# projet_pcb_bluepill_f103.net
KiCad netlist of a schematic drawn in Altium Designer
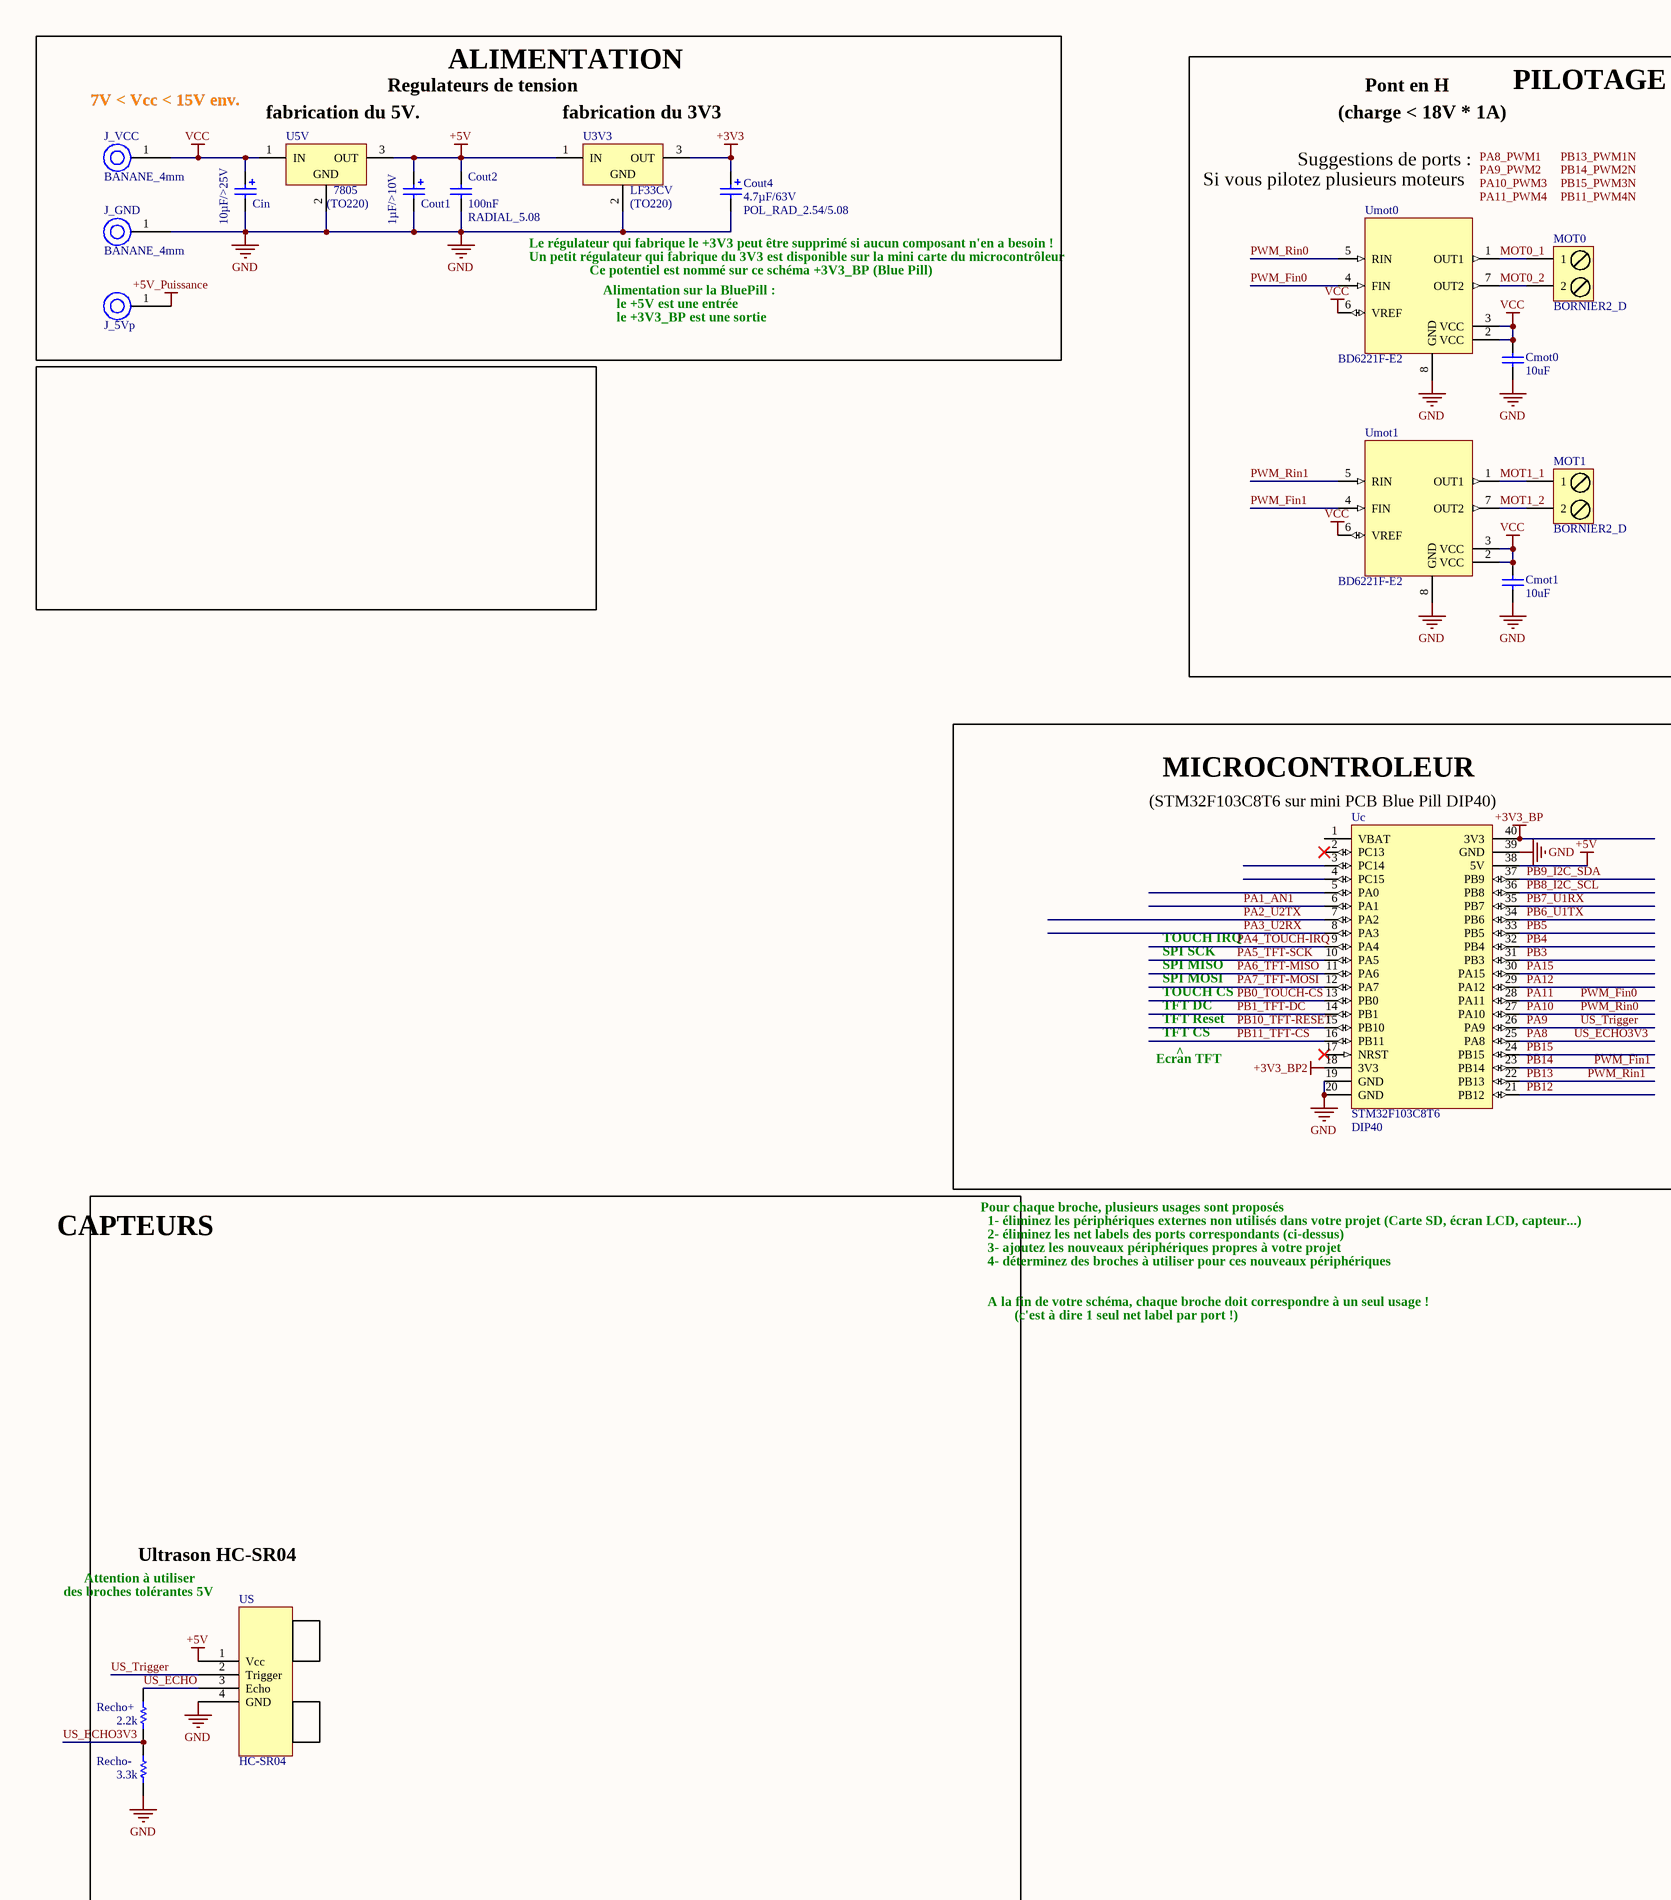
[diagram p0: projet_pcb_bluepill_f103.SchDoc, left]
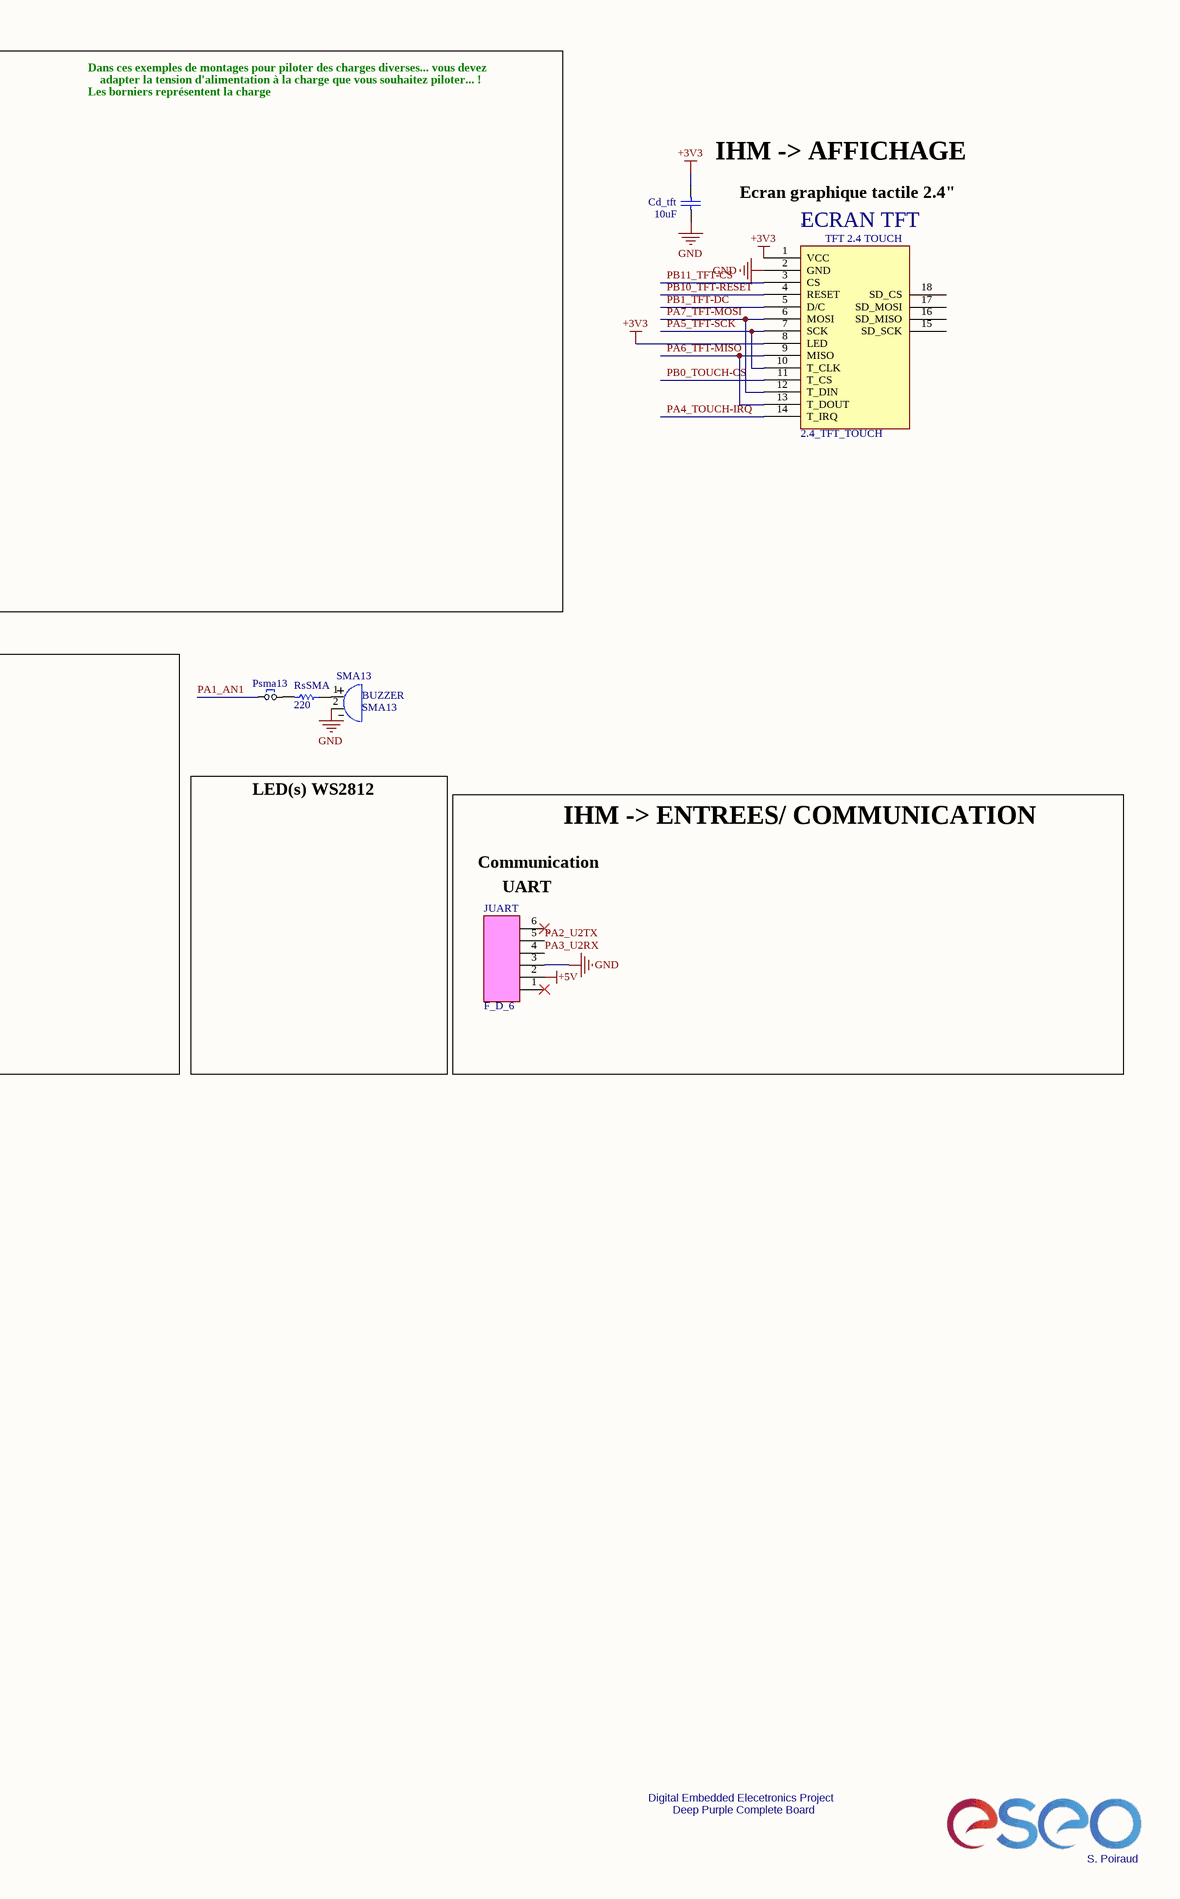
[diagram p1: projet_pcb_bluepill_f103.SchDoc, right]

(export (version "E")
  (design (tool "Eeschema 10.0.6"))
  (components
    (comp (ref "*")
      (value "2.4_TFT_TOUCH")
      (footprint "2.4_TFT_TOUCH")
      (libsource (lib "_ROBOT") (part "2.4_TFT_TOUCH"))
    )
    (comp (ref "Cd_tft")
      (value "10uF")
      (footprint "CONDENSATEUR_POLARISE_ELECTROLYTIQUE_RADIAL_2.54/5.08")
      (description "Capacitor")
      (fields (field (name "PUBLISHER") "Altium Limited"))
      (libsource (lib "_ROBOT") (part "Condensateur"))
    )
    (comp (ref "Cin")
      (value "10µF/>25V")
      (footprint "CONDENSATEUR_POLARISE_ELECTROLYTIQUE_RADIAL_2.0/5.08")
      (description "CONDENSATEUR POLARISE ELECTROLYTIQUE RADIAL 2.0/5.08")
      (fields (field (name "Comment") "CONDENSATEUR_POL_ELECTROLY_RAD_2.0/5.08"))
      (libsource (lib "composants passifs") (part "CONDENSATEUR_POL_ELECTROLY_RAD_2.0/5.08"))
    )
    (comp (ref "Cmot0")
      (value "10uF")
      (footprint "CONDENSATEUR_POLARISE_ELECTROLYTIQUE_RADIAL_2.0/5.08")
      (description "Capacitor")
      (fields (field (name "PUBLISHER") "Altium Limited"))
      (libsource (lib "_ROBOT") (part "Condensateur"))
    )
    (comp (ref "Cmot1")
      (value "10uF")
      (footprint "CONDENSATEUR_POLARISE_ELECTROLYTIQUE_RADIAL_2.0/5.08")
      (description "Capacitor")
      (fields (field (name "PUBLISHER") "Altium Limited"))
      (libsource (lib "_ROBOT") (part "Condensateur"))
    )
    (comp (ref "Cout1")
      (value "1µF/>10V")
      (footprint "CONDENSATEUR_POLARISE_ELECTROLYTIQUE_RADIAL_2.0/5.08")
      (description "CONDENSATEUR POLARISE ELECTROLYTIQUE RADIAL 2.0/5.08")
      (fields (field (name "Comment") "CONDENSATEUR_POL_ELECTROLY_RAD_2.0/5.08"))
      (libsource (lib "composants passifs") (part "CONDENSATEUR_POL_ELECTROLY_RAD_2.0/5.08"))
    )
    (comp (ref "Cout2")
      (value "100nF")
      (footprint "CONDENSATEUR_CERAMIQUE_RADIAL_5.08")
      (description "CONDENSATEUR TRAVERSANT CERAMIQUE RADIAL 5.08mm")
      (fields (field (name "TYPE") "RADIAL_5.08") (field (name "Comment") "CONDENSATEUR_CER_RAD_5.08"))
      (libsource (lib "composants passifs") (part "CONDENSATEUR_CER_RAD_5.08"))
    )
    (comp (ref "Cout4")
      (value "4.7µF/63V")
      (footprint "CONDENSATEUR_POLARISE_ELECTROLYTIQUE_RADIAL_2.54/5.08")
      (description "CONDENSATEUR POLARISE ELECTROLYTIQUE RADIAL 2.54/5.08")
      (fields
        (field (name "TYPE") "POL_RAD_2.54/5.08")
        (field (name "Comment") "CONDENSATEUR_POL_ELECTROLY_RAD_2.54/5.08")
      )
      (libsource (lib "composants passifs") (part "CONDENSATEUR_POL_ELECTROLY_RAD_2.54/5.08"))
    )
    (comp (ref "JUART")
      (value "BARRETTE_6 CONTACTS_1 RANGEE_FEMELLE_DROITE")
      (footprint "BARRETTE_6_F_D")
      (description "BARRETTE 6 CONTACTS 1 RANGEE FEMELLE DROITE")
      (fields (field (name "TYPE") "F_D_6"))
      (libsource (lib "connecteurs") (part "BARRETTE_6 CONTACTS_1 RANGEE_FEMELLE_DROITE"))
    )
    (comp (ref "J_5Vp")
      (value "DOUILLE BANANE 4mm")
      (footprint "DOUILLE_BANANE_4mm")
      (description "DOUILLE BANANE 4 mm")
      (libsource (lib "connecteurs") (part "DOUILLE_BANANE_4mm"))
    )
    (comp (ref "J_GND")
      (value "DOUILLE BANANE 4mm")
      (footprint "DOUILLE_BANANE_4mm")
      (description "DOUILLE BANANE 4 mm")
      (fields (field (name "TYPE") "BANANE_4mm"))
      (libsource (lib "connecteurs") (part "DOUILLE_BANANE_4mm"))
    )
    (comp (ref "J_VCC")
      (value "DOUILLE BANANE 4mm")
      (footprint "DOUILLE_BANANE_4mm")
      (description "DOUILLE BANANE 4 mm")
      (fields (field (name "TYPE") "BANANE_4mm"))
      (libsource (lib "connecteurs") (part "DOUILLE_BANANE_4mm"))
    )
    (comp (ref "MOT0")
      (value "BORNIER2 DROIT A VIS")
      (footprint "BORNIER2_A_VIS")
      (description "BORNIER 2 PLOTS DROIT A VIS 5.08mm")
      (fields (field (name "TYPE") "BORNIER2_D"))
      (libsource (lib "connecteurs") (part "BORNIER2_DROIT_A VIS"))
    )
    (comp (ref "MOT1")
      (value "BORNIER2 DROIT A VIS")
      (footprint "BORNIER2_A_VIS")
      (description "BORNIER 2 PLOTS DROIT A VIS 5.08mm")
      (fields (field (name "TYPE") "BORNIER2_D"))
      (libsource (lib "connecteurs") (part "BORNIER2_DROIT_A VIS"))
    )
    (comp (ref "Psma13")
      (value "Jumper SIP 2.54")
      (footprint "HDR1X2")
      (description "Jumper SIP2.54")
      (libsource (lib "Connecteur") (part "Jumper SIP2.54"))
    )
    (comp (ref "Recho+")
      (value "2.2k")
      (footprint "R1206_N")
      (description "Resistor")
      (fields (field (name "PUBLISHER") "Altium Limited"))
      (libsource (lib "_ROBOT") (part "Resistor"))
    )
    (comp (ref "Recho-")
      (value "3.3k")
      (footprint "R1206_N")
      (description "Resistor")
      (fields (field (name "PUBLISHER") "Altium Limited"))
      (libsource (lib "_ROBOT") (part "Resistor"))
    )
    (comp (ref "RsSMA")
      (value "220")
      (footprint "R1206_N")
      (description "Resistor")
      (fields (field (name "PUBLISHER") "Altium Limited"))
      (libsource (lib "_ROBOT") (part "Resistor"))
    )
    (comp (ref "SMA13")
      (value "SMA13")
      (footprint "BUZZER_SMA13")
      (description "BUZZER SMA13")
      (fields (field (name "TYPE") "BUZZER") (field (name "Comment") "BUZZER_SMA13"))
      (libsource (lib "electromecanique") (part "BUZZER_SMA13"))
    )
    (comp (ref "U3V3")
      (value "REGULATEUR_TO220_78XX")
      (footprint "REGULATEUR_TO220_78XX")
      (description "REGULATEUR DE TENSION POSITIVE 78XX BOITIER TO220")
      (fields (field (name "TYPE") "LF33CV") (field (name "PACKAGE") "(TO220)"))
      (libsource (lib "composants actifs") (part "REGULATEUR_TO220_78XX"))
    )
    (comp (ref "U5V")
      (value "REGULATEUR_TO220_78XX")
      (footprint "REGULATEUR_TO220_78XX")
      (description "REGULATEUR DE TENSION POSITIVE 78XX BOITIER TO220")
      (fields (field (name "TYPE") "7805") (field (name "PACKAGE") "(TO220)"))
      (libsource (lib "composants actifs") (part "REGULATEUR_TO220_78XX"))
    )
    (comp (ref "Uc")
      (value "STM32F103C8T6/PCB_DIP40")
      (footprint "STM32F103C8T6_DIP40")
      (fields (field (name "TYPE") "STM32F103C8T6") (field (name "PACKAGE") "DIP40"))
      (libsource (lib "circuits integres") (part "STM32F103C8T6/PCB_DIP40"))
    )
    (comp (ref "Umot0")
      (value "BD6221F-E2")
      (footprint "SOIC8_PAS=1.27_LARG=4_LONG=5")
      (description "H Bridge - 2A")
      (libsource (lib "Circuit intégré") (part "BD6220F"))
    )
    (comp (ref "Umot1")
      (value "BD6221F-E2")
      (footprint "SOIC8_PAS=1.27_LARG=4_LONG=5")
      (description "H Bridge - 2A")
      (libsource (lib "Circuit intégré") (part "BD6220F"))
    )
    (comp (ref "US") (value "HC-SR04") (footprint "HC-SR04") (libsource (lib "DEEP") (part "HC-SR04")))
  )
  (nets
    (net (code "1") (name "+3V3") (class "Default")
      (node (ref "*") (pin "1") (pinfunction "VCC_1") (pintype "passive"))
      (node (ref "*") (pin "8") (pinfunction "LED_8") (pintype "passive"))
      (node (ref "Cd_tft") (pin "1") (pinfunction "1_1") (pintype "passive"))
      (node (ref "Cout4") (pin "1") (pinfunction "1_1") (pintype "passive"))
      (node (ref "U3V3") (pin "3") (pinfunction "OUT_3") (pintype "power_in"))
    )
    (net (code "2") (name "+3V3_BP") (class "Default")
      (node (ref "Uc") (pin "40") (pinfunction "3V3_40") (pintype "power_in"))
    )
    (net (code "3") (name "+3V3_BP2") (class "Default")
      (node (ref "Uc") (pin "18") (pinfunction "3V3_18") (pintype "power_in"))
    )
    (net (code "4") (name "+5V") (class "Default")
      (node (ref "Cout1") (pin "1") (pinfunction "1_1") (pintype "passive"))
      (node (ref "Cout2") (pin "2") (pinfunction "2_2") (pintype "passive"))
      (node (ref "JUART") (pin "2") (pinfunction "2_2") (pintype "passive"))
      (node (ref "U3V3") (pin "1") (pinfunction "IN_1") (pintype "power_in"))
      (node (ref "U5V") (pin "3") (pinfunction "OUT_3") (pintype "power_in"))
      (node (ref "US") (pin "1") (pinfunction "Vcc_1") (pintype "passive"))
      (node (ref "Uc") (pin "38") (pinfunction "5V_38") (pintype "power_in"))
    )
    (net (code "5") (name "+5V_Puissance") (class "Default")
      (node (ref "J_5Vp") (pin "1") (pinfunction "1_1") (pintype "passive"))
    )
    (net (code "6") (name "/MOT0_1") (class "Default")
      (node (ref "MOT0") (pin "1") (pinfunction "1_1") (pintype "passive"))
      (node (ref "Umot0") (pin "1") (pinfunction "OUT1_1") (pintype "output"))
    )
    (net (code "7") (name "/MOT0_2") (class "Default")
      (node (ref "MOT0") (pin "2") (pinfunction "2_2") (pintype "passive"))
      (node (ref "Umot0") (pin "7") (pinfunction "OUT2_7") (pintype "output"))
    )
    (net (code "8") (name "/MOT1_1") (class "Default")
      (node (ref "MOT1") (pin "1") (pinfunction "1_1") (pintype "passive"))
      (node (ref "Umot1") (pin "1") (pinfunction "OUT1_1") (pintype "output"))
    )
    (net (code "9") (name "/MOT1_2") (class "Default")
      (node (ref "MOT1") (pin "2") (pinfunction "2_2") (pintype "passive"))
      (node (ref "Umot1") (pin "7") (pinfunction "OUT2_7") (pintype "output"))
    )
    (net (code "10") (name "/PA1_AN1") (class "Default")
      (node (ref "Psma13") (pin "1") (pinfunction "1_1") (pintype "passive"))
      (node (ref "Uc") (pin "6") (pinfunction "PA1_6") (pintype "bidirectional"))
    )
    (net (code "11") (name "/PA2_U2TX") (class "Default")
      (node (ref "JUART") (pin "5") (pinfunction "5_5") (pintype "passive"))
      (node (ref "Uc") (pin "7") (pinfunction "PA2_7") (pintype "bidirectional"))
    )
    (net (code "12") (name "/PA3_U2RX") (class "Default")
      (node (ref "JUART") (pin "4") (pinfunction "4_4") (pintype "passive"))
      (node (ref "Uc") (pin "8") (pinfunction "PA3_8") (pintype "bidirectional"))
    )
    (net (code "13") (name "/PA4_TOUCH-IRQ") (class "Default")
      (node (ref "*") (pin "14") (pinfunction "T_IRQ_14") (pintype "passive"))
      (node (ref "Uc") (pin "9") (pinfunction "PA4_9") (pintype "bidirectional"))
    )
    (net (code "14") (name "/PA5_TFT-SCK") (class "Default")
      (node (ref "*") (pin "10") (pinfunction "T_CLK_10") (pintype "passive"))
      (node (ref "*") (pin "7") (pinfunction "SCK_7") (pintype "passive"))
      (node (ref "Uc") (pin "10") (pinfunction "PA5_10") (pintype "bidirectional"))
    )
    (net (code "15") (name "/PA6_TFT-MISO") (class "Default")
      (node (ref "*") (pin "13") (pinfunction "T_DOUT_13") (pintype "passive"))
      (node (ref "*") (pin "9") (pinfunction "MISO_9") (pintype "passive"))
      (node (ref "Uc") (pin "11") (pinfunction "PA6_11") (pintype "bidirectional"))
    )
    (net (code "16") (name "/PA7_TFT-MOSI") (class "Default")
      (node (ref "*") (pin "12") (pinfunction "T_DIN_12") (pintype "passive"))
      (node (ref "*") (pin "6") (pinfunction "MOSI_6") (pintype "passive"))
      (node (ref "Uc") (pin "12") (pinfunction "PA7_12") (pintype "bidirectional"))
    )
    (net (code "17") (name "/PA8") (class "Default")
      (node (ref "Recho+") (pin "1") (pinfunction "1_1") (pintype "passive"))
      (node (ref "Recho-") (pin "2") (pinfunction "2_2") (pintype "passive"))
      (node (ref "Uc") (pin "25") (pinfunction "PA8_25") (pintype "bidirectional"))
    )
    (net (code "19") (name "/PA9") (class "Default")
      (node (ref "US") (pin "2") (pinfunction "Trigger_2") (pintype "passive"))
      (node (ref "Uc") (pin "26") (pinfunction "PA9_26") (pintype "bidirectional"))
    )
    (net (code "21") (name "/PA10") (class "Default")
      (node (ref "Uc") (pin "27") (pinfunction "PA10_27") (pintype "bidirectional"))
      (node (ref "Umot0") (pin "5") (pinfunction "RIN_5") (pintype "input"))
    )
    (net (code "23") (name "/PA11") (class "Default")
      (node (ref "Uc") (pin "28") (pinfunction "PA11_28") (pintype "bidirectional"))
      (node (ref "Umot0") (pin "4") (pinfunction "FIN_4") (pintype "input"))
    )
    (net (code "25") (name "/PA12") (class "Default")
      (node (ref "Uc") (pin "29") (pinfunction "PA12_29") (pintype "bidirectional"))
    )
    (net (code "26") (name "/PA15") (class "Default")
      (node (ref "Uc") (pin "30") (pinfunction "PA15_30") (pintype "bidirectional"))
    )
    (net (code "27") (name "/PB0_TOUCH-CS") (class "Default")
      (node (ref "*") (pin "11") (pinfunction "T_CS_11") (pintype "passive"))
      (node (ref "Uc") (pin "13") (pinfunction "PB0_13") (pintype "bidirectional"))
    )
    (net (code "28") (name "/PB1_TFT-DC") (class "Default")
      (node (ref "*") (pin "5") (pinfunction "D/C_5") (pintype "passive"))
      (node (ref "Uc") (pin "14") (pinfunction "PB1_14") (pintype "bidirectional"))
    )
    (net (code "29") (name "/PB3") (class "Default")
      (node (ref "Uc") (pin "31") (pinfunction "PB3_31") (pintype "bidirectional"))
    )
    (net (code "30") (name "/PB4") (class "Default")
      (node (ref "Uc") (pin "32") (pinfunction "PB4_32") (pintype "bidirectional"))
    )
    (net (code "31") (name "/PB5") (class "Default")
      (node (ref "Uc") (pin "33") (pinfunction "PB5_33") (pintype "bidirectional"))
    )
    (net (code "32") (name "/PB6_U1TX") (class "Default")
      (node (ref "Uc") (pin "34") (pinfunction "PB6_34") (pintype "bidirectional"))
    )
    (net (code "33") (name "/PB7_U1RX") (class "Default")
      (node (ref "Uc") (pin "35") (pinfunction "PB7_35") (pintype "bidirectional"))
    )
    (net (code "34") (name "/PB8_I2C_SCL") (class "Default")
      (node (ref "Uc") (pin "36") (pinfunction "PB8_36") (pintype "bidirectional"))
    )
    (net (code "35") (name "/PB9_I2C_SDA") (class "Default")
      (node (ref "Uc") (pin "37") (pinfunction "PB9_37") (pintype "bidirectional"))
    )
    (net (code "36") (name "/PB10_TFT-RESET") (class "Default")
      (node (ref "*") (pin "4") (pinfunction "RESET_4") (pintype "passive"))
      (node (ref "Uc") (pin "15") (pinfunction "PB10_15") (pintype "bidirectional"))
    )
    (net (code "38") (name "/PB11_TFT-CS") (class "Default")
      (node (ref "*") (pin "3") (pinfunction "CS_3") (pintype "passive"))
      (node (ref "Uc") (pin "16") (pinfunction "PB11_16") (pintype "bidirectional"))
    )
    (net (code "39") (name "/PB12") (class "Default")
      (node (ref "Uc") (pin "21") (pinfunction "PB12_21") (pintype "bidirectional"))
    )
    (net (code "40") (name "/PB13") (class "Default")
      (node (ref "Uc") (pin "22") (pinfunction "PB13_22") (pintype "bidirectional"))
      (node (ref "Umot1") (pin "5") (pinfunction "RIN_5") (pintype "input"))
    )
    (net (code "42") (name "/PB14") (class "Default")
      (node (ref "Uc") (pin "23") (pinfunction "PB14_23") (pintype "bidirectional"))
      (node (ref "Umot1") (pin "4") (pinfunction "FIN_4") (pintype "input"))
    )
    (net (code "44") (name "/PB15") (class "Default")
      (node (ref "Uc") (pin "24") (pinfunction "PB15_24") (pintype "bidirectional"))
    )
    (net (code "46") (name "/US_ECHO") (class "Default")
      (node (ref "Recho+") (pin "2") (pinfunction "2_2") (pintype "passive"))
      (node (ref "US") (pin "3") (pinfunction "Echo_3") (pintype "passive"))
    )
    (net (code "47") (name "GND") (class "Default")
      (node (ref "*") (pin "2") (pinfunction "GND_2") (pintype "passive"))
      (node (ref "Cd_tft") (pin "2") (pinfunction "2_2") (pintype "passive"))
      (node (ref "Cin") (pin "2") (pinfunction "2_2") (pintype "passive"))
      (node (ref "Cmot0") (pin "1") (pinfunction "1_1") (pintype "passive"))
      (node (ref "Cmot1") (pin "1") (pinfunction "1_1") (pintype "passive"))
      (node (ref "Cout1") (pin "2") (pinfunction "2_2") (pintype "passive"))
      (node (ref "Cout2") (pin "1") (pinfunction "1_1") (pintype "passive"))
      (node (ref "Cout4") (pin "2") (pinfunction "2_2") (pintype "passive"))
      (node (ref "JUART") (pin "3") (pinfunction "3_3") (pintype "passive"))
      (node (ref "J_GND") (pin "1") (pinfunction "1_1") (pintype "passive"))
      (node (ref "Recho-") (pin "1") (pinfunction "1_1") (pintype "passive"))
      (node (ref "SMA13") (pin "2") (pinfunction "2_2") (pintype "passive"))
      (node (ref "U3V3") (pin "2") (pinfunction "GND_2") (pintype "power_in"))
      (node (ref "U5V") (pin "2") (pinfunction "GND_2") (pintype "power_in"))
      (node (ref "US") (pin "4") (pinfunction "GND_4") (pintype "passive"))
      (node (ref "Uc") (pin "19") (pinfunction "GND_19") (pintype "power_in"))
      (node (ref "Uc") (pin "20") (pinfunction "GND_20") (pintype "power_in"))
      (node (ref "Uc") (pin "39") (pinfunction "GND_39") (pintype "power_in"))
      (node (ref "Umot0") (pin "8") (pinfunction "GND_8") (pintype "power_in"))
      (node (ref "Umot1") (pin "8") (pinfunction "GND_8") (pintype "power_in"))
    )
    (net (code "48") (name "Net-(Psma13-Pad2)") (class "Default")
      (node (ref "Psma13") (pin "2") (pinfunction "2_2") (pintype "passive"))
      (node (ref "RsSMA") (pin "2") (pinfunction "2_2") (pintype "passive"))
    )
    (net (code "49") (name "Net-(RsSMA-Pad1)") (class "Default")
      (node (ref "RsSMA") (pin "1") (pinfunction "1_1") (pintype "passive"))
      (node (ref "SMA13") (pin "1") (pinfunction "1_1") (pintype "passive"))
    )
    (net (code "50") (name "VCC") (class "Default")
      (node (ref "Cin") (pin "1") (pinfunction "1_1") (pintype "passive"))
      (node (ref "Cmot0") (pin "2") (pinfunction "2_2") (pintype "passive"))
      (node (ref "Cmot1") (pin "2") (pinfunction "2_2") (pintype "passive"))
      (node (ref "J_VCC") (pin "1") (pinfunction "1_1") (pintype "passive"))
      (node (ref "U5V") (pin "1") (pinfunction "IN_1") (pintype "power_in"))
      (node (ref "Umot0") (pin "2") (pinfunction "VCC_2") (pintype "power_in"))
      (node (ref "Umot0") (pin "3") (pinfunction "VCC_3") (pintype "power_in"))
      (node (ref "Umot0") (pin "6") (pinfunction "VREF_6") (pintype "bidirectional"))
      (node (ref "Umot1") (pin "2") (pinfunction "VCC_2") (pintype "power_in"))
      (node (ref "Umot1") (pin "3") (pinfunction "VCC_3") (pintype "power_in"))
      (node (ref "Umot1") (pin "6") (pinfunction "VREF_6") (pintype "bidirectional"))
    )
    (net (code "51") (name "unconnected-(*-SD_CS-Pad18)") (class "Default")
      (node (ref "*") (pin "18") (pinfunction "SD_CS_18") (pintype "passive"))
    )
    (net (code "52") (name "unconnected-(*-SD_MISO-Pad16)") (class "Default")
      (node (ref "*") (pin "16") (pinfunction "SD_MISO_16") (pintype "passive"))
    )
    (net (code "53") (name "unconnected-(*-SD_MOSI-Pad17)") (class "Default")
      (node (ref "*") (pin "17") (pinfunction "SD_MOSI_17") (pintype "passive"))
    )
    (net (code "54") (name "unconnected-(*-SD_SCK-Pad15)") (class "Default")
      (node (ref "*") (pin "15") (pinfunction "SD_SCK_15") (pintype "passive"))
    )
    (net (code "55") (name "unconnected-(JUART-Pad1)") (class "Default")
      (node (ref "JUART") (pin "1") (pinfunction "1_1") (pintype "passive+no_connect"))
    )
    (net (code "56") (name "unconnected-(JUART-Pad6)") (class "Default")
      (node (ref "JUART") (pin "6") (pinfunction "6_6") (pintype "passive+no_connect"))
    )
    (net (code "57") (name "unconnected-(Uc-NRST-Pad17)") (class "Default")
      (node (ref "Uc") (pin "17") (pinfunction "NRST_17") (pintype "input+no_connect"))
    )
    (net (code "58") (name "unconnected-(Uc-PA0-Pad5)") (class "Default")
      (node (ref "Uc") (pin "5") (pinfunction "PA0_5") (pintype "bidirectional"))
    )
    (net (code "59") (name "unconnected-(Uc-PC13-Pad2)") (class "Default")
      (node (ref "Uc") (pin "2") (pinfunction "PC13_2") (pintype "bidirectional+no_connect"))
    )
    (net (code "60") (name "unconnected-(Uc-PC14-Pad3)") (class "Default")
      (node (ref "Uc") (pin "3") (pinfunction "PC14_3") (pintype "bidirectional"))
    )
    (net (code "61") (name "unconnected-(Uc-PC15-Pad4)") (class "Default")
      (node (ref "Uc") (pin "4") (pinfunction "PC15_4") (pintype "bidirectional"))
    )
    (net (code "62") (name "unconnected-(Uc-VBAT-Pad1)") (class "Default")
      (node (ref "Uc") (pin "1") (pinfunction "VBAT_1") (pintype "power_in"))
    )
  )
)
